# O2_Clone_V_Orig.net
KiCad netlist of a schematic drawn in EAGLE
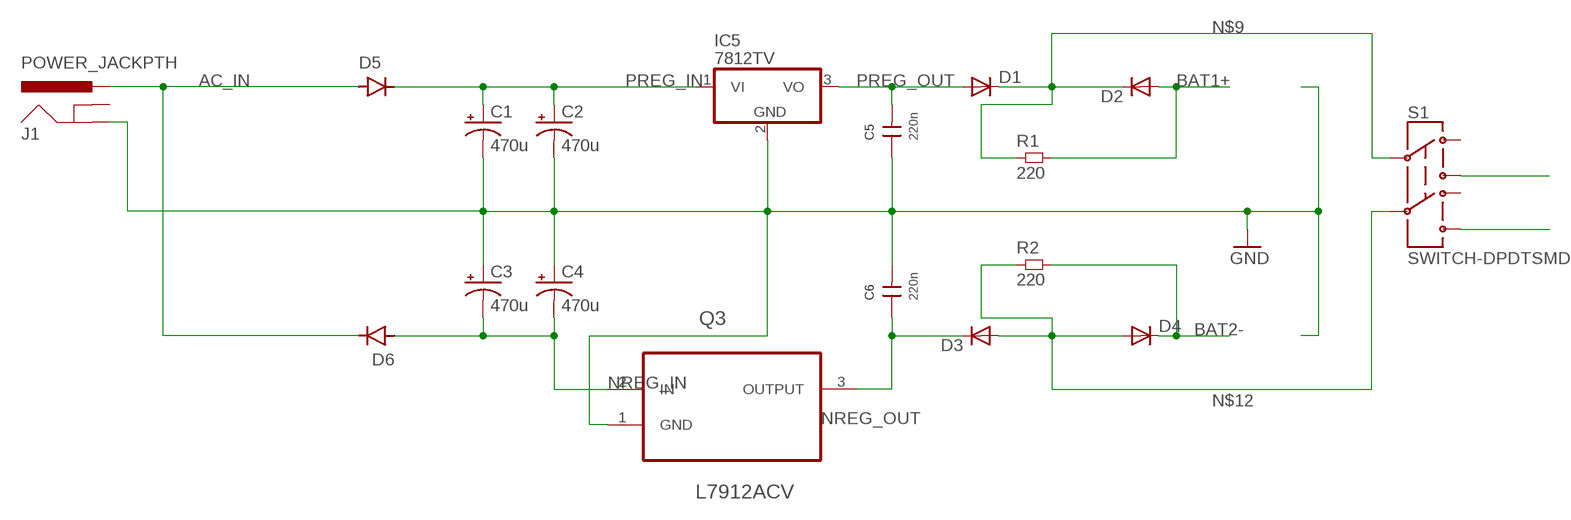
[diagram p0: schematic, sheet 1]
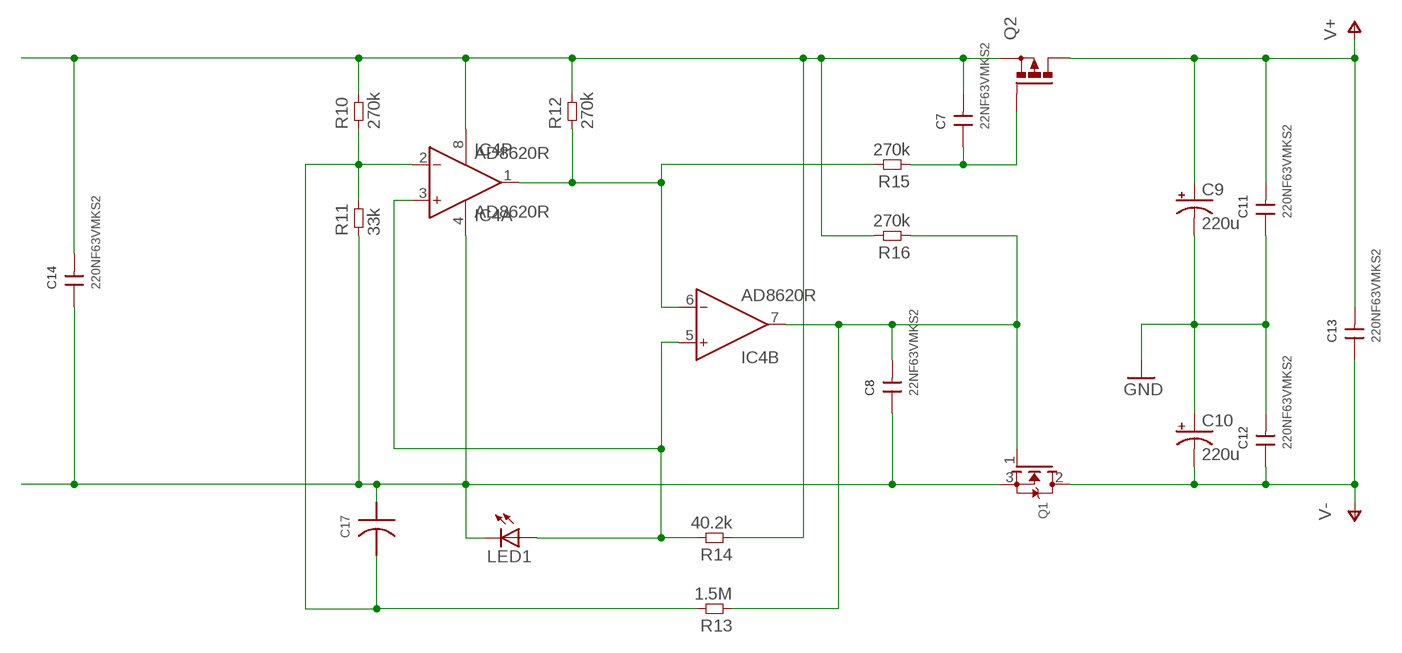
[diagram p1: schematic, sheet 2]
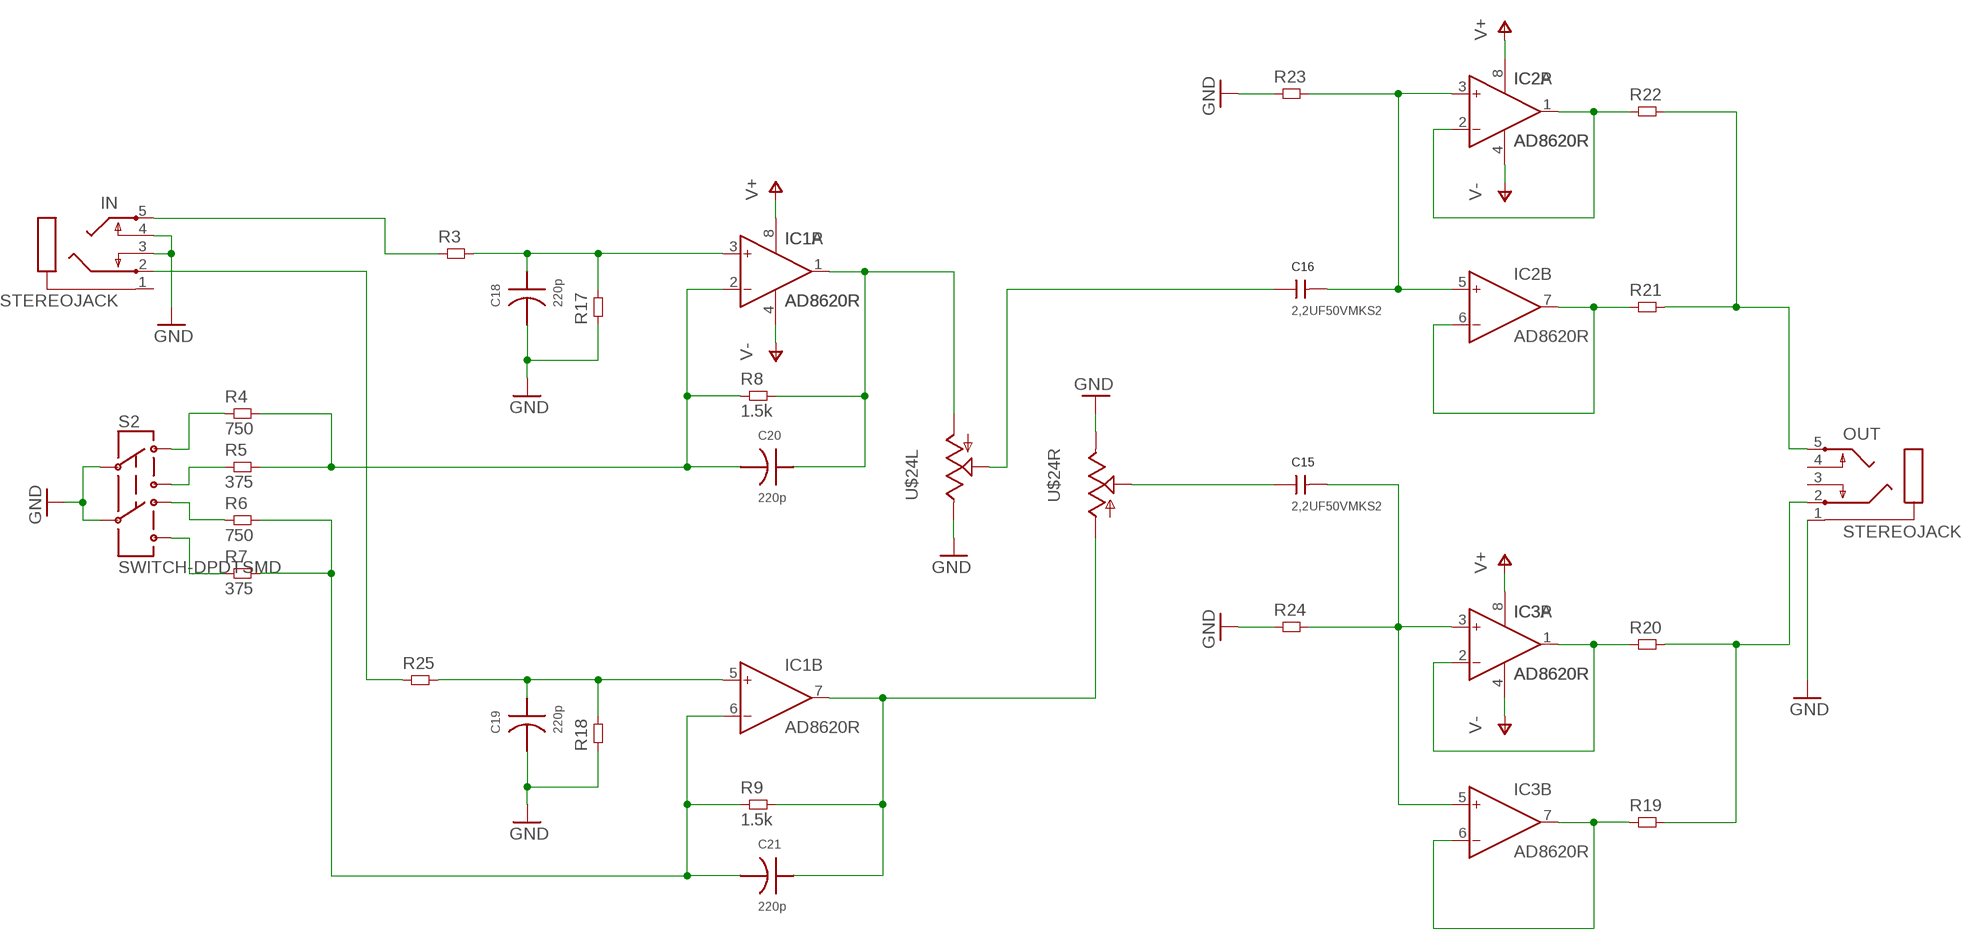
[diagram p2: schematic, sheet 3]

(export (version "E")
  (design (tool "Eeschema 10.0.6"))
  (components
    (comp (ref "C7")
      (value "22NF63VMKS2")
      (footprint "eagle-import:2,5X6,5RM5,0")
      (libsource (lib "eagle-import") (part "22NF63VMKS2"))
    )
    (comp (ref "C8")
      (value "22NF63VMKS2")
      (footprint "eagle-import:2,5X6,5RM5,0")
      (libsource (lib "eagle-import") (part "22NF63VMKS2"))
    )
    (comp (ref "C9")
      (value "220u")
      (footprint "eagle-import:E3,5-8")
      (libsource (lib "eagle-import") (part "CPOL-USE3.5-8"))
    )
    (comp (ref "C10")
      (value "220u")
      (footprint "eagle-import:E3,5-8")
      (libsource (lib "eagle-import") (part "CPOL-USE3.5-8"))
    )
    (comp (ref "C11")
      (value "220NF63VMKS2")
      (footprint "eagle-import:3,0X7,5RM5,0")
      (libsource (lib "eagle-import") (part "220NF63VMKS2"))
    )
    (comp (ref "C12")
      (value "220NF63VMKS2")
      (footprint "eagle-import:3,0X7,5RM5,0")
      (libsource (lib "eagle-import") (part "220NF63VMKS2"))
    )
    (comp (ref "C13")
      (value "220NF63VMKS2")
      (footprint "eagle-import:3,0X7,5RM5,0")
      (libsource (lib "eagle-import") (part "220NF63VMKS2"))
    )
    (comp (ref "C14")
      (value "220NF63VMKS2")
      (footprint "eagle-import:3,0X7,5RM5,0")
      (libsource (lib "eagle-import") (part "220NF63VMKS2"))
    )
    (comp (ref "C17")
      (value "PCAP0805LEVEL3")
      (footprint "eagle-import:R0805")
      (libsource (lib "eagle-import") (part "PCAP0805LEVEL3"))
    )
    (comp (ref "IC4")
      (value "AD8620R")
      (footprint "eagle-import:SO8")
      (fields (field (name "MF") "ALTERA CORPORATION") (field (name "MPN") "AD8620ARZ"))
      (libsource (lib "eagle-import") (part "AD8620R"))
    )
    (comp (ref "LED1")
      (value "LED3MM")
      (footprint "eagle-import:LED3MM")
      (libsource (lib "eagle-import") (part "LED3MM"))
    )
    (comp (ref "Q1")
      (value "MOSFET-NGDS_TO220V")
      (footprint "eagle-import:TO220V")
      (libsource (lib "eagle-import") (part "MOSFET-NGDS_TO220V"))
    )
    (comp (ref "Q2")
      (value "PMOSFET_PTO220BV")
      (footprint "eagle-import:TO220BV")
      (libsource (lib "eagle-import") (part "PMOSFET_PTO220BV"))
    )
    (comp (ref "R10")
      (value "270k")
      (footprint "eagle-import:0603L3")
      (libsource (lib "eagle-import") (part "RES0603L3"))
    )
    (comp (ref "R11")
      (value "33k")
      (footprint "eagle-import:0603L3")
      (libsource (lib "eagle-import") (part "RES0603L3"))
    )
    (comp (ref "R12")
      (value "270k")
      (footprint "eagle-import:0603L3")
      (libsource (lib "eagle-import") (part "RES0603L3"))
    )
    (comp (ref "R13")
      (value "1.5M")
      (footprint "eagle-import:0603L3")
      (libsource (lib "eagle-import") (part "RES0603L3"))
    )
    (comp (ref "R14")
      (value "40.2k")
      (footprint "eagle-import:0603L3")
      (libsource (lib "eagle-import") (part "RES0603L3"))
    )
    (comp (ref "R15")
      (value "270k")
      (footprint "eagle-import:0603L3")
      (libsource (lib "eagle-import") (part "RES0603L3"))
    )
    (comp (ref "R16")
      (value "270k")
      (footprint "eagle-import:0603L3")
      (libsource (lib "eagle-import") (part "RES0603L3"))
    )
    (comp (ref "C1")
      (value "470u")
      (footprint "eagle-import:E5-10,5")
      (libsource (lib "eagle-import") (part "CPOL-USE5-10.5"))
    )
    (comp (ref "C2")
      (value "470u")
      (footprint "eagle-import:E5-10,5")
      (libsource (lib "eagle-import") (part "CPOL-USE5-10.5"))
    )
    (comp (ref "C3")
      (value "470u")
      (footprint "eagle-import:E5-10,5")
      (libsource (lib "eagle-import") (part "CPOL-USE5-10.5"))
    )
    (comp (ref "C4")
      (value "470u")
      (footprint "eagle-import:E5-10,5")
      (libsource (lib "eagle-import") (part "CPOL-USE5-10.5"))
    )
    (comp (ref "C5")
      (value "220n")
      (footprint "eagle-import:3,0X7,5RM5,0")
      (libsource (lib "eagle-import") (part "220NF63VMKS2"))
    )
    (comp (ref "C6")
      (value "220n")
      (footprint "eagle-import:3,0X7,5RM5,0")
      (libsource (lib "eagle-import") (part "220NF63VMKS2"))
    )
    (comp (ref "D1")
      (value "DIODE-SMB")
      (footprint "eagle-import:SMB")
      (libsource (lib "eagle-import") (part "DIODE-SMB"))
    )
    (comp (ref "D2")
      (value "DIODE-SMB")
      (footprint "eagle-import:SMB")
      (libsource (lib "eagle-import") (part "DIODE-SMB"))
    )
    (comp (ref "D3")
      (value "DIODE-SMB")
      (footprint "eagle-import:SMB")
      (libsource (lib "eagle-import") (part "DIODE-SMB"))
    )
    (comp (ref "D4")
      (value "DIODE-SMB")
      (footprint "eagle-import:SMB")
      (libsource (lib "eagle-import") (part "DIODE-SMB"))
    )
    (comp (ref "D5")
      (value "DIODE-SMX")
      (footprint "eagle-import:SMX")
      (libsource (lib "eagle-import") (part "DIODE-SMX"))
    )
    (comp (ref "D6")
      (value "DIODE-SMX")
      (footprint "eagle-import:SMX")
      (libsource (lib "eagle-import") (part "DIODE-SMX"))
    )
    (comp (ref "IC5")
      (value "7812TV")
      (footprint "eagle-import:TO220V")
      (libsource (lib "eagle-import") (part "78TV12"))
    )
    (comp (ref "J1")
      (value "POWER_JACKPTH")
      (footprint "eagle-import:POWER_JACK_PTH")
      (libsource (lib "eagle-import") (part "POWER_JACKPTH"))
    )
    (comp (ref "Q3")
      (value "L7912ACV")
      (footprint "eagle-import:TO254P450X1020X1935-3P")
      (libsource (lib "eagle-import") (part "L7912ACV"))
    )
    (comp (ref "R1")
      (value "220")
      (footprint "eagle-import:0603L3")
      (libsource (lib "eagle-import") (part "RES0603L3"))
    )
    (comp (ref "R2")
      (value "220")
      (footprint "eagle-import:0603L3")
      (libsource (lib "eagle-import") (part "RES0603L3"))
    )
    (comp (ref "S1")
      (value "SWITCH-DPDTSMD")
      (footprint "eagle-import:AYZ0202")
      (libsource (lib "eagle-import") (part "SWITCH-DPDTSMD"))
    )
    (comp (ref "C15")
      (value "2,2UF50VMKS2")
      (footprint "eagle-import:7,2X13,0RM5,0")
      (libsource (lib "eagle-import") (part "2,2UF50VMKS2"))
    )
    (comp (ref "C16")
      (value "2,2UF50VMKS2")
      (footprint "eagle-import:7,2X13,0RM5,0")
      (libsource (lib "eagle-import") (part "2,2UF50VMKS2"))
    )
    (comp (ref "C18")
      (value "220p")
      (footprint "eagle-import:R0603")
      (libsource (lib "eagle-import") (part "PCAP0603LEVEL3"))
    )
    (comp (ref "C19")
      (value "220p")
      (footprint "eagle-import:R0603")
      (libsource (lib "eagle-import") (part "PCAP0603LEVEL3"))
    )
    (comp (ref "C20")
      (value "220p")
      (footprint "eagle-import:R0603")
      (libsource (lib "eagle-import") (part "PCAP0603LEVEL3"))
    )
    (comp (ref "C21")
      (value "220p")
      (footprint "eagle-import:R0603")
      (libsource (lib "eagle-import") (part "PCAP0603LEVEL3"))
    )
    (comp (ref "IC1")
      (value "AD8620R")
      (footprint "eagle-import:SO8")
      (fields (field (name "MF") "ALTERA CORPORATION") (field (name "MPN") "AD8620ARZ"))
      (libsource (lib "eagle-import") (part "AD8620R"))
    )
    (comp (ref "IC2")
      (value "AD8620R")
      (footprint "eagle-import:SO8")
      (fields (field (name "MF") "ALTERA CORPORATION") (field (name "MPN") "AD8620ARZ"))
      (libsource (lib "eagle-import") (part "AD8620R"))
    )
    (comp (ref "IC3")
      (value "AD8620R")
      (footprint "eagle-import:SO8")
      (fields (field (name "MF") "ALTERA CORPORATION") (field (name "MPN") "AD8620ARZ"))
      (libsource (lib "eagle-import") (part "AD8620R"))
    )
    (comp (ref "IN")
      (value "STEREOJACK")
      (footprint "eagle-import:STX3100")
      (libsource (lib "eagle-import") (part "STEREOJACK"))
    )
    (comp (ref "OUT")
      (value "STEREOJACK")
      (footprint "eagle-import:STX3100")
      (libsource (lib "eagle-import") (part "STEREOJACK"))
    )
    (comp (ref "R3")
      (value "RES0603L3")
      (footprint "eagle-import:0603L3")
      (libsource (lib "eagle-import") (part "RES0603L3"))
    )
    (comp (ref "R4")
      (value "750")
      (footprint "eagle-import:0603L3")
      (libsource (lib "eagle-import") (part "RES0603L3"))
    )
    (comp (ref "R5")
      (value "375")
      (footprint "eagle-import:0603L3")
      (libsource (lib "eagle-import") (part "RES0603L3"))
    )
    (comp (ref "R6")
      (value "750")
      (footprint "eagle-import:0603L3")
      (libsource (lib "eagle-import") (part "RES0603L3"))
    )
    (comp (ref "R7")
      (value "375")
      (footprint "eagle-import:0603L3")
      (libsource (lib "eagle-import") (part "RES0603L3"))
    )
    (comp (ref "R8")
      (value "1.5k")
      (footprint "eagle-import:0603L3")
      (libsource (lib "eagle-import") (part "RES0603L3"))
    )
    (comp (ref "R9")
      (value "1.5k")
      (footprint "eagle-import:0603L3")
      (libsource (lib "eagle-import") (part "RES0603L3"))
    )
    (comp (ref "R17")
      (value "RES0603L3")
      (footprint "eagle-import:0603L3")
      (libsource (lib "eagle-import") (part "RES0603L3"))
    )
    (comp (ref "R18")
      (value "RES0603L3")
      (footprint "eagle-import:0603L3")
      (libsource (lib "eagle-import") (part "RES0603L3"))
    )
    (comp (ref "R19")
      (value "RES0603L3")
      (footprint "eagle-import:0603L3")
      (libsource (lib "eagle-import") (part "RES0603L3"))
    )
    (comp (ref "R20")
      (value "RES0603L3")
      (footprint "eagle-import:0603L3")
      (libsource (lib "eagle-import") (part "RES0603L3"))
    )
    (comp (ref "R21")
      (value "RES0603L3")
      (footprint "eagle-import:0603L3")
      (libsource (lib "eagle-import") (part "RES0603L3"))
    )
    (comp (ref "R22")
      (value "RES0603L3")
      (footprint "eagle-import:0603L3")
      (libsource (lib "eagle-import") (part "RES0603L3"))
    )
    (comp (ref "R23")
      (value "RES0603L3")
      (footprint "eagle-import:0603L3")
      (libsource (lib "eagle-import") (part "RES0603L3"))
    )
    (comp (ref "R24")
      (value "RES0603L3")
      (footprint "eagle-import:0603L3")
      (libsource (lib "eagle-import") (part "RES0603L3"))
    )
    (comp (ref "R25")
      (value "RES0603L3")
      (footprint "eagle-import:0603L3")
      (libsource (lib "eagle-import") (part "RES0603L3"))
    )
    (comp (ref "S2")
      (value "SWITCH-DPDTSMD")
      (footprint "eagle-import:AYZ0202")
      (libsource (lib "eagle-import") (part "SWITCH-DPDTSMD"))
    )
    (comp (ref "U$24")
      (value "ALPS_RK0971221Z0N")
      (footprint "eagle-import:ALPS_RK0971221Z0X")
      (libsource (lib "eagle-import") (part "ALPS_RK0971221Z0N"))
    )
  )
  (nets
    (net (code "1") (name "AC_IN") (class "Default")
      (node (ref "D5") (pin "1") (pinfunction "ANODE_1") (pintype "bidirectional"))
      (node (ref "D6") (pin "2") (pinfunction "CATHODE_2") (pintype "bidirectional"))
      (node (ref "J1") (pin "PWR") (pinfunction "PWR_PWR") (pintype "bidirectional"))
    )
    (net (code "2") (name "BAT1+") (class "Default")
      (node (ref "D2") (pin "A") (pinfunction "A_A") (pintype "passive"))
      (node (ref "R1") (pin "P$2") (pinfunction "2_P$2") (pintype "bidirectional"))
    )
    (net (code "3") (name "BAT2-") (class "Default")
      (node (ref "D4") (pin "C") (pinfunction "C_C") (pintype "passive"))
      (node (ref "R2") (pin "P$2") (pinfunction "2_P$2") (pintype "bidirectional"))
    )
    (net (code "4") (name "GND") (class "Default")
      (node (ref "C1") (pin "-") (pinfunction "-_-") (pintype "passive"))
      (node (ref "C10") (pin "+") (pinfunction "+_+") (pintype "passive"))
      (node (ref "C11") (pin "1") (pinfunction "1_1") (pintype "passive"))
      (node (ref "C12") (pin "2") (pinfunction "2_2") (pintype "passive"))
      (node (ref "C18") (pin "P$1") (pinfunction "P$1_P$1") (pintype "bidirectional"))
      (node (ref "C19") (pin "P$1") (pinfunction "P$1_P$1") (pintype "bidirectional"))
      (node (ref "C2") (pin "-") (pinfunction "-_-") (pintype "passive"))
      (node (ref "C3") (pin "+") (pinfunction "+_+") (pintype "passive"))
      (node (ref "C4") (pin "+") (pinfunction "+_+") (pintype "passive"))
      (node (ref "C5") (pin "1") (pinfunction "1_1") (pintype "passive"))
      (node (ref "C6") (pin "2") (pinfunction "2_2") (pintype "passive"))
      (node (ref "C9") (pin "-") (pinfunction "-_-") (pintype "passive"))
      (node (ref "IC5") (pin "2") (pinfunction "GND_2") (pintype "passive"))
      (node (ref "IN") (pin "3") (pinfunction "3_3") (pintype "passive"))
      (node (ref "IN") (pin "4") (pinfunction "4_4") (pintype "passive"))
      (node (ref "J1") (pin "GND") (pinfunction "GND_GND") (pintype "bidirectional"))
      (node (ref "OUT") (pin "1") (pinfunction "1_1") (pintype "passive"))
      (node (ref "Q3") (pin "1") (pinfunction "GND_1") (pintype "passive"))
      (node (ref "R17") (pin "P$1") (pinfunction "1_P$1") (pintype "bidirectional"))
      (node (ref "R18") (pin "P$1") (pinfunction "1_P$1") (pintype "bidirectional"))
      (node (ref "R23") (pin "P$1") (pinfunction "1_P$1") (pintype "bidirectional"))
      (node (ref "R24") (pin "P$1") (pinfunction "1_P$1") (pintype "bidirectional"))
      (node (ref "S2") (pin "2") (pinfunction "2_2") (pintype "bidirectional"))
      (node (ref "S2") (pin "5") (pinfunction "5_5") (pintype "bidirectional"))
      (node (ref "U$24") (pin "I1") (pinfunction "3_I1") (pintype "passive"))
      (node (ref "U$24") (pin "I2") (pinfunction "3_I2") (pintype "passive"))
    )
    (net (code "5") (name "N$9") (class "Default")
      (node (ref "D1") (pin "C") (pinfunction "C_C") (pintype "passive"))
      (node (ref "D2") (pin "C") (pinfunction "C_C") (pintype "passive"))
      (node (ref "R1") (pin "P$1") (pinfunction "1_P$1") (pintype "bidirectional"))
      (node (ref "S1") (pin "2") (pinfunction "2_2") (pintype "bidirectional"))
    )
    (net (code "6") (name "N$12") (class "Default")
      (node (ref "D3") (pin "A") (pinfunction "A_A") (pintype "passive"))
      (node (ref "D4") (pin "A") (pinfunction "A_A") (pintype "passive"))
      (node (ref "R2") (pin "P$1") (pinfunction "1_P$1") (pintype "bidirectional"))
      (node (ref "S1") (pin "5") (pinfunction "5_5") (pintype "bidirectional"))
    )
    (net (code "7") (name "NREG_IN") (class "Default")
      (node (ref "C3") (pin "-") (pinfunction "-_-") (pintype "passive"))
      (node (ref "C4") (pin "-") (pinfunction "-_-") (pintype "passive"))
      (node (ref "D6") (pin "1") (pinfunction "ANODE_1") (pintype "bidirectional"))
      (node (ref "Q3") (pin "2") (pinfunction "IN_2") (pintype "input"))
    )
    (net (code "8") (name "NREG_OUT") (class "Default")
      (node (ref "C6") (pin "1") (pinfunction "1_1") (pintype "passive"))
      (node (ref "D3") (pin "C") (pinfunction "C_C") (pintype "passive"))
      (node (ref "Q3") (pin "3") (pinfunction "OUTPUT_3") (pintype "output"))
    )
    (net (code "9") (name "Net-(IC1A-IN+)") (class "Default")
      (node (ref "C18") (pin "P$2") (pinfunction "P$2_P$2") (pintype "bidirectional"))
      (node (ref "IC1") (pin "3") (pinfunction "IN+_3") (pintype "input"))
      (node (ref "R17") (pin "P$2") (pinfunction "2_P$2") (pintype "bidirectional"))
      (node (ref "R3") (pin "P$2") (pinfunction "2_P$2") (pintype "bidirectional"))
    )
    (net (code "10") (name "Net-(IC1A-IN-)") (class "Default")
      (node (ref "C20") (pin "P$1") (pinfunction "P$1_P$1") (pintype "bidirectional"))
      (node (ref "IC1") (pin "2") (pinfunction "IN-_2") (pintype "input"))
      (node (ref "R4") (pin "P$2") (pinfunction "2_P$2") (pintype "bidirectional"))
      (node (ref "R5") (pin "P$2") (pinfunction "2_P$2") (pintype "bidirectional"))
      (node (ref "R8") (pin "P$1") (pinfunction "1_P$1") (pintype "bidirectional"))
    )
    (net (code "11") (name "Net-(IC1A-OUT)") (class "Default")
      (node (ref "C20") (pin "P$2") (pinfunction "P$2_P$2") (pintype "bidirectional"))
      (node (ref "IC1") (pin "1") (pinfunction "OUT_1") (pintype "output"))
      (node (ref "R8") (pin "P$2") (pinfunction "2_P$2") (pintype "bidirectional"))
      (node (ref "U$24") (pin "G1") (pinfunction "1_G1") (pintype "passive"))
    )
    (net (code "12") (name "Net-(IC1B-IN+)") (class "Default")
      (node (ref "C19") (pin "P$2") (pinfunction "P$2_P$2") (pintype "bidirectional"))
      (node (ref "IC1") (pin "5") (pinfunction "IN+_5") (pintype "input"))
      (node (ref "R18") (pin "P$2") (pinfunction "2_P$2") (pintype "bidirectional"))
      (node (ref "R25") (pin "P$2") (pinfunction "2_P$2") (pintype "bidirectional"))
    )
    (net (code "13") (name "Net-(IC1B-IN-)") (class "Default")
      (node (ref "C21") (pin "P$1") (pinfunction "P$1_P$1") (pintype "bidirectional"))
      (node (ref "IC1") (pin "6") (pinfunction "IN-_6") (pintype "input"))
      (node (ref "R6") (pin "P$2") (pinfunction "2_P$2") (pintype "bidirectional"))
      (node (ref "R7") (pin "P$2") (pinfunction "2_P$2") (pintype "bidirectional"))
      (node (ref "R9") (pin "P$1") (pinfunction "1_P$1") (pintype "bidirectional"))
    )
    (net (code "14") (name "Net-(IC1B-OUT)") (class "Default")
      (node (ref "C21") (pin "P$2") (pinfunction "P$2_P$2") (pintype "bidirectional"))
      (node (ref "IC1") (pin "7") (pinfunction "OUT_7") (pintype "output"))
      (node (ref "R9") (pin "P$2") (pinfunction "2_P$2") (pintype "bidirectional"))
      (node (ref "U$24") (pin "G2") (pinfunction "1_G2") (pintype "passive"))
    )
    (net (code "15") (name "Net-(IC2A-IN+)") (class "Default")
      (node (ref "C16") (pin "2") (pinfunction "2_2") (pintype "passive"))
      (node (ref "IC2") (pin "3") (pinfunction "IN+_3") (pintype "input"))
      (node (ref "IC2") (pin "5") (pinfunction "IN+_5") (pintype "input"))
      (node (ref "R23") (pin "P$2") (pinfunction "2_P$2") (pintype "bidirectional"))
    )
    (net (code "16") (name "Net-(IC2A-IN-)") (class "Default")
      (node (ref "IC2") (pin "1") (pinfunction "OUT_1") (pintype "output"))
      (node (ref "IC2") (pin "2") (pinfunction "IN-_2") (pintype "input"))
      (node (ref "R22") (pin "P$1") (pinfunction "1_P$1") (pintype "bidirectional"))
    )
    (net (code "17") (name "Net-(IC2B-IN-)") (class "Default")
      (node (ref "IC2") (pin "6") (pinfunction "IN-_6") (pintype "input"))
      (node (ref "IC2") (pin "7") (pinfunction "OUT_7") (pintype "output"))
      (node (ref "R21") (pin "P$1") (pinfunction "1_P$1") (pintype "bidirectional"))
    )
    (net (code "18") (name "Net-(IC3A-IN+)") (class "Default")
      (node (ref "C15") (pin "2") (pinfunction "2_2") (pintype "passive"))
      (node (ref "IC3") (pin "3") (pinfunction "IN+_3") (pintype "input"))
      (node (ref "IC3") (pin "5") (pinfunction "IN+_5") (pintype "input"))
      (node (ref "R24") (pin "P$2") (pinfunction "2_P$2") (pintype "bidirectional"))
    )
    (net (code "19") (name "Net-(IC3A-IN-)") (class "Default")
      (node (ref "IC3") (pin "1") (pinfunction "OUT_1") (pintype "output"))
      (node (ref "IC3") (pin "2") (pinfunction "IN-_2") (pintype "input"))
      (node (ref "R20") (pin "P$1") (pinfunction "1_P$1") (pintype "bidirectional"))
    )
    (net (code "20") (name "Net-(IC3B-IN-)") (class "Default")
      (node (ref "IC3") (pin "6") (pinfunction "IN-_6") (pintype "input"))
      (node (ref "IC3") (pin "7") (pinfunction "OUT_7") (pintype "output"))
      (node (ref "R19") (pin "P$1") (pinfunction "1_P$1") (pintype "bidirectional"))
    )
    (net (code "21") (name "Net-(IC4A-IN+)") (class "Default")
      (node (ref "IC4") (pin "3") (pinfunction "IN+_3") (pintype "input"))
      (node (ref "IC4") (pin "5") (pinfunction "IN+_5") (pintype "input"))
      (node (ref "LED1") (pin "A") (pinfunction "A_A") (pintype "passive"))
      (node (ref "R14") (pin "P$2") (pinfunction "2_P$2") (pintype "bidirectional"))
    )
    (net (code "22") (name "Net-(IC4A-IN-)") (class "Default")
      (node (ref "C17") (pin "P$1") (pinfunction "P$1_P$1") (pintype "bidirectional"))
      (node (ref "IC4") (pin "2") (pinfunction "IN-_2") (pintype "input"))
      (node (ref "R10") (pin "P$1") (pinfunction "1_P$1") (pintype "bidirectional"))
      (node (ref "R11") (pin "P$2") (pinfunction "2_P$2") (pintype "bidirectional"))
      (node (ref "R13") (pin "P$2") (pinfunction "2_P$2") (pintype "bidirectional"))
    )
    (net (code "23") (name "Net-(IC4A-OUT)") (class "Default")
      (node (ref "IC4") (pin "1") (pinfunction "OUT_1") (pintype "output"))
      (node (ref "IC4") (pin "6") (pinfunction "IN-_6") (pintype "input"))
      (node (ref "R12") (pin "P$1") (pinfunction "1_P$1") (pintype "bidirectional"))
      (node (ref "R15") (pin "P$2") (pinfunction "2_P$2") (pintype "bidirectional"))
    )
    (net (code "24") (name "Net-(IC4B-OUT)") (class "Default")
      (node (ref "C8") (pin "2") (pinfunction "2_2") (pintype "passive"))
      (node (ref "IC4") (pin "7") (pinfunction "OUT_7") (pintype "output"))
      (node (ref "Q1") (pin "1") (pinfunction "G_1") (pintype "bidirectional"))
      (node (ref "R13") (pin "P$1") (pinfunction "1_P$1") (pintype "bidirectional"))
      (node (ref "R16") (pin "P$1") (pinfunction "1_P$1") (pintype "bidirectional"))
    )
    (net (code "25") (name "Net-(IC4C-V+)") (class "Default")
      (node (ref "C14") (pin "2") (pinfunction "2_2") (pintype "passive"))
      (node (ref "C7") (pin "2") (pinfunction "2_2") (pintype "passive"))
      (node (ref "IC4") (pin "8") (pinfunction "V+_8") (pintype "power_in"))
      (node (ref "Q2") (pin "S") (pinfunction "S_S") (pintype "passive"))
      (node (ref "R10") (pin "P$2") (pinfunction "2_P$2") (pintype "bidirectional"))
      (node (ref "R12") (pin "P$2") (pinfunction "2_P$2") (pintype "bidirectional"))
      (node (ref "R14") (pin "P$1") (pinfunction "1_P$1") (pintype "bidirectional"))
      (node (ref "R16") (pin "P$2") (pinfunction "2_P$2") (pintype "bidirectional"))
    )
    (net (code "26") (name "Net-(IC4C-V-)") (class "Default")
      (node (ref "C14") (pin "1") (pinfunction "1_1") (pintype "passive"))
      (node (ref "C17") (pin "P$2") (pinfunction "P$2_P$2") (pintype "bidirectional"))
      (node (ref "C8") (pin "1") (pinfunction "1_1") (pintype "passive"))
      (node (ref "IC4") (pin "4") (pinfunction "V-_4") (pintype "power_in"))
      (node (ref "LED1") (pin "K") (pinfunction "C_K") (pintype "passive"))
      (node (ref "Q1") (pin "3") (pinfunction "S_3") (pintype "bidirectional"))
      (node (ref "R11") (pin "P$1") (pinfunction "1_P$1") (pintype "bidirectional"))
    )
    (net (code "27") (name "Net-(R3-1)") (class "Default")
      (node (ref "IN") (pin "5") (pinfunction "5_5") (pintype "passive"))
      (node (ref "R3") (pin "P$1") (pinfunction "1_P$1") (pintype "bidirectional"))
    )
    (net (code "28") (name "Net-(R4-1)") (class "Default")
      (node (ref "R4") (pin "P$1") (pinfunction "1_P$1") (pintype "bidirectional"))
      (node (ref "S2") (pin "1") (pinfunction "1_1") (pintype "bidirectional"))
    )
    (net (code "29") (name "Net-(R5-1)") (class "Default")
      (node (ref "R5") (pin "P$1") (pinfunction "1_P$1") (pintype "bidirectional"))
      (node (ref "S2") (pin "3") (pinfunction "3_3") (pintype "bidirectional"))
    )
    (net (code "30") (name "Net-(R6-1)") (class "Default")
      (node (ref "R6") (pin "P$1") (pinfunction "1_P$1") (pintype "bidirectional"))
      (node (ref "S2") (pin "4") (pinfunction "4_4") (pintype "bidirectional"))
    )
    (net (code "31") (name "Net-(R7-1)") (class "Default")
      (node (ref "R7") (pin "P$1") (pinfunction "1_P$1") (pintype "bidirectional"))
      (node (ref "S2") (pin "6") (pinfunction "6_6") (pintype "bidirectional"))
    )
    (net (code "32") (name "Net-(R15-1)") (class "Default")
      (node (ref "C7") (pin "1") (pinfunction "1_1") (pintype "passive"))
      (node (ref "Q2") (pin "G") (pinfunction "G_G") (pintype "passive"))
      (node (ref "R15") (pin "P$1") (pinfunction "1_P$1") (pintype "bidirectional"))
    )
    (net (code "33") (name "Net-(R19-2)") (class "Default")
      (node (ref "OUT") (pin "2") (pinfunction "2_2") (pintype "passive"))
      (node (ref "R19") (pin "P$2") (pinfunction "2_P$2") (pintype "bidirectional"))
      (node (ref "R20") (pin "P$2") (pinfunction "2_P$2") (pintype "bidirectional"))
    )
    (net (code "34") (name "Net-(R21-2)") (class "Default")
      (node (ref "OUT") (pin "5") (pinfunction "5_5") (pintype "passive"))
      (node (ref "R21") (pin "P$2") (pinfunction "2_P$2") (pintype "bidirectional"))
      (node (ref "R22") (pin "P$2") (pinfunction "2_P$2") (pintype "bidirectional"))
    )
    (net (code "35") (name "Net-(R25-1)") (class "Default")
      (node (ref "IN") (pin "2") (pinfunction "2_2") (pintype "passive"))
      (node (ref "R25") (pin "P$1") (pinfunction "1_P$1") (pintype "bidirectional"))
    )
    (net (code "36") (name "Net-(U$24B-2)") (class "Default")
      (node (ref "C16") (pin "1") (pinfunction "1_1") (pintype "passive"))
      (node (ref "U$24") (pin "O1") (pinfunction "2_O1") (pintype "passive"))
    )
    (net (code "37") (name "Net-(U$24C-2)") (class "Default")
      (node (ref "C15") (pin "1") (pinfunction "1_1") (pintype "passive"))
      (node (ref "U$24") (pin "O2") (pinfunction "2_O2") (pintype "passive"))
    )
    (net (code "38") (name "PREG_IN") (class "Default")
      (node (ref "C1") (pin "+") (pinfunction "+_+") (pintype "passive"))
      (node (ref "C2") (pin "+") (pinfunction "+_+") (pintype "passive"))
      (node (ref "D5") (pin "2") (pinfunction "CATHODE_2") (pintype "bidirectional"))
      (node (ref "IC5") (pin "1") (pinfunction "VI_1") (pintype "input"))
    )
    (net (code "39") (name "PREG_OUT") (class "Default")
      (node (ref "C5") (pin "2") (pinfunction "2_2") (pintype "passive"))
      (node (ref "D1") (pin "A") (pinfunction "A_A") (pintype "passive"))
      (node (ref "IC5") (pin "3") (pinfunction "VO_3") (pintype "passive"))
    )
    (net (code "40") (name "V+") (class "Default")
      (node (ref "C11") (pin "2") (pinfunction "2_2") (pintype "passive"))
      (node (ref "C13") (pin "2") (pinfunction "2_2") (pintype "passive"))
      (node (ref "C9") (pin "+") (pinfunction "+_+") (pintype "passive"))
      (node (ref "IC1") (pin "8") (pinfunction "V+_8") (pintype "power_in"))
      (node (ref "IC2") (pin "8") (pinfunction "V+_8") (pintype "power_in"))
      (node (ref "IC3") (pin "8") (pinfunction "V+_8") (pintype "power_in"))
      (node (ref "Q2") (pin "D") (pinfunction "D_D") (pintype "passive"))
    )
    (net (code "41") (name "V-") (class "Default")
      (node (ref "C10") (pin "-") (pinfunction "-_-") (pintype "passive"))
      (node (ref "C12") (pin "1") (pinfunction "1_1") (pintype "passive"))
      (node (ref "C13") (pin "1") (pinfunction "1_1") (pintype "passive"))
      (node (ref "IC1") (pin "4") (pinfunction "V-_4") (pintype "power_in"))
      (node (ref "IC2") (pin "4") (pinfunction "V-_4") (pintype "power_in"))
      (node (ref "IC3") (pin "4") (pinfunction "V-_4") (pintype "power_in"))
      (node (ref "Q1") (pin "2") (pinfunction "D_2") (pintype "bidirectional"))
    )
    (net (code "42") (name "unconnected-(IN-Pad1)") (class "Default")
      (node (ref "IN") (pin "1") (pinfunction "1_1") (pintype "passive"))
    )
    (net (code "43") (name "unconnected-(J1-PadGNDBREAK)") (class "Default")
      (node (ref "J1") (pin "GNDBREAK") (pinfunction "GNDBREAK_GNDBREAK") (pintype "bidirectional"))
    )
    (net (code "44") (name "unconnected-(OUT-Pad3)") (class "Default")
      (node (ref "OUT") (pin "3") (pinfunction "3_3") (pintype "passive"))
    )
    (net (code "45") (name "unconnected-(OUT-Pad4)") (class "Default")
      (node (ref "OUT") (pin "4") (pinfunction "4_4") (pintype "passive"))
    )
    (net (code "46") (name "unconnected-(S1-Pad1)") (class "Default")
      (node (ref "S1") (pin "1") (pinfunction "1_1") (pintype "bidirectional"))
    )
    (net (code "47") (name "unconnected-(S1-Pad3)") (class "Default")
      (node (ref "S1") (pin "3") (pinfunction "3_3") (pintype "bidirectional"))
    )
    (net (code "48") (name "unconnected-(S1-Pad4)") (class "Default")
      (node (ref "S1") (pin "4") (pinfunction "4_4") (pintype "bidirectional"))
    )
    (net (code "49") (name "unconnected-(S1-Pad6)") (class "Default")
      (node (ref "S1") (pin "6") (pinfunction "6_6") (pintype "bidirectional"))
    )
  )
)
